# work_table_light.net
KiCad netlist of a schematic drawn in EAGLE
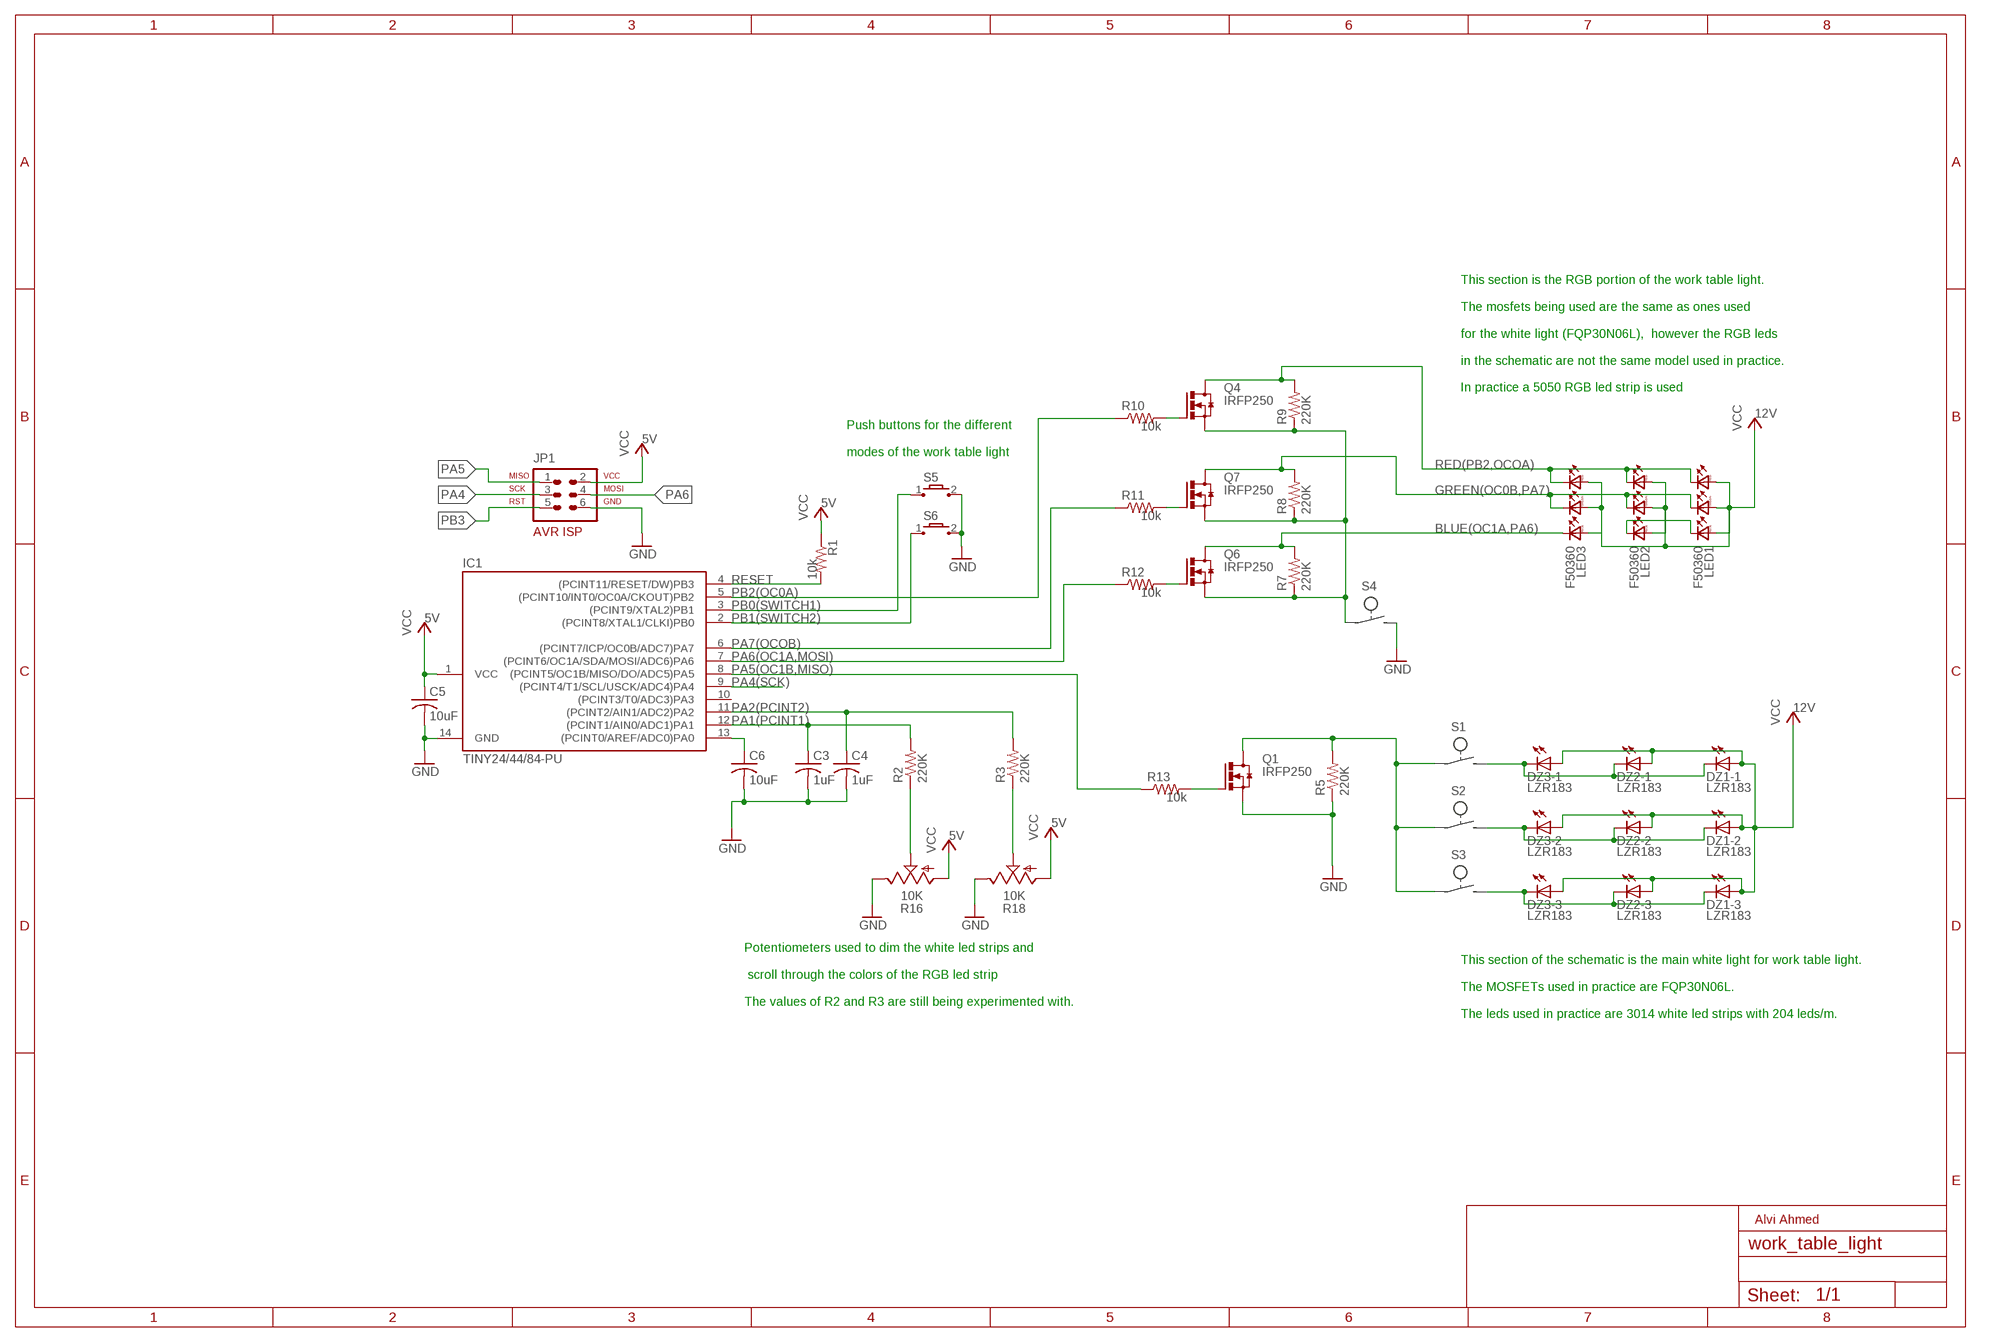
[diagram p0: schematic, sheet 1]

(export (version "E")
  (design (tool "Eeschema 10.0.6"))
  (components
    (comp (ref "C3")
      (value "1uF")
      (footprint "eagle-import:C025-024X044")
      (libsource (lib "eagle-import") (part "C-US025-024X044"))
    )
    (comp (ref "C4")
      (value "1uF")
      (footprint "eagle-import:C025-024X044")
      (libsource (lib "eagle-import") (part "C-US025-024X044"))
    )
    (comp (ref "C5")
      (value "10uF")
      (footprint "eagle-import:C025-024X044")
      (libsource (lib "eagle-import") (part "C-US025-024X044"))
    )
    (comp (ref "C6")
      (value "10uF")
      (footprint "eagle-import:C025-024X044")
      (libsource (lib "eagle-import") (part "C-US025-024X044"))
    )
    (comp (ref "DZ1")
      (value "LZR183")
      (footprint "eagle-import:LZR183")
      (libsource (lib "eagle-import") (part "LZR183"))
    )
    (comp (ref "DZ2")
      (value "LZR183")
      (footprint "eagle-import:LZR183")
      (libsource (lib "eagle-import") (part "LZR183"))
    )
    (comp (ref "DZ3")
      (value "LZR183")
      (footprint "eagle-import:LZR183")
      (libsource (lib "eagle-import") (part "LZR183"))
    )
    (comp (ref "IC1")
      (value "TINY24/44/84-PU")
      (footprint "eagle-import:DIL14")
      (libsource (lib "eagle-import") (part "TINY24/44/84-PU"))
    )
    (comp (ref "JP1")
      (value "AVR-ISP-6VERT")
      (footprint "eagle-import:AVR-ISP-6")
      (libsource (lib "eagle-import") (part "AVR-ISP-6VERT"))
    )
    (comp (ref "LED1")
      (value "F50360")
      (footprint "eagle-import:F50360")
      (libsource (lib "eagle-import") (part "F50360"))
    )
    (comp (ref "LED2")
      (value "F50360")
      (footprint "eagle-import:F50360")
      (libsource (lib "eagle-import") (part "F50360"))
    )
    (comp (ref "LED3")
      (value "F50360")
      (footprint "eagle-import:F50360")
      (libsource (lib "eagle-import") (part "F50360"))
    )
    (comp (ref "Q1")
      (value "IRFP250")
      (footprint "eagle-import:TO-247AD-V")
      (libsource (lib "eagle-import") (part "IRFP250"))
    )
    (comp (ref "Q4")
      (value "IRFP250")
      (footprint "eagle-import:TO-247AD-V")
      (libsource (lib "eagle-import") (part "IRFP250"))
    )
    (comp (ref "Q6")
      (value "IRFP250")
      (footprint "eagle-import:TO-247AD-V")
      (libsource (lib "eagle-import") (part "IRFP250"))
    )
    (comp (ref "Q7")
      (value "IRFP250")
      (footprint "eagle-import:TO-247AD-V")
      (libsource (lib "eagle-import") (part "IRFP250"))
    )
    (comp (ref "R1")
      (value "R-US_0204/5")
      (footprint "eagle-import:0204_5")
      (fields (field (name "SPICEPREFIX") "R") (field (name "SPICEPREFIX_1") "10k"))
      (libsource (lib "eagle-import") (part "R-US_0204/5"))
    )
    (comp (ref "R2")
      (value "220K")
      (footprint "eagle-import:0207_10")
      (libsource (lib "eagle-import") (part "resistor_348_R-US_0207/10"))
    )
    (comp (ref "R3")
      (value "220K")
      (footprint "eagle-import:0207_10")
      (libsource (lib "eagle-import") (part "resistor_348_R-US_0207/10"))
    )
    (comp (ref "R5")
      (value "220K")
      (footprint "eagle-import:0207_10")
      (libsource (lib "eagle-import") (part "resistor_348_R-US_0207/10"))
    )
    (comp (ref "R7")
      (value "220K")
      (footprint "eagle-import:0207_10")
      (libsource (lib "eagle-import") (part "resistor_348_R-US_0207/10"))
    )
    (comp (ref "R8")
      (value "220K")
      (footprint "eagle-import:0207_10")
      (libsource (lib "eagle-import") (part "resistor_348_R-US_0207/10"))
    )
    (comp (ref "R9")
      (value "220K")
      (footprint "eagle-import:0207_10")
      (libsource (lib "eagle-import") (part "resistor_348_R-US_0207/10"))
    )
    (comp (ref "R10")
      (value "R-US_0204/5")
      (footprint "eagle-import:0204_5")
      (fields (field (name "SPICEPREFIX") "R") (field (name "SPICEPREFIX_1") "10k"))
      (libsource (lib "eagle-import") (part "R-US_0204/5"))
    )
    (comp (ref "R11")
      (value "R-US_0204/5")
      (footprint "eagle-import:0204_5")
      (fields (field (name "SPICEPREFIX") "R") (field (name "SPICEPREFIX_1") "10k"))
      (libsource (lib "eagle-import") (part "R-US_0204/5"))
    )
    (comp (ref "R12")
      (value "R-US_0204/5")
      (footprint "eagle-import:0204_5")
      (fields (field (name "SPICEPREFIX") "R") (field (name "SPICEPREFIX_1") "10k"))
      (libsource (lib "eagle-import") (part "R-US_0204/5"))
    )
    (comp (ref "R13")
      (value "R-US_0204/5")
      (footprint "eagle-import:0204_5")
      (fields (field (name "SPICEPREFIX") "R") (field (name "SPICEPREFIX_1") "10k"))
      (libsource (lib "eagle-import") (part "R-US_0204/5"))
    )
    (comp (ref "R16")
      (value "10K")
      (footprint "eagle-import:CIP20C-6MM")
      (libsource (lib "eagle-import") (part "TRIM_US-CIP20C-6MM"))
    )
    (comp (ref "R18")
      (value "10K")
      (footprint "eagle-import:CIP20C-6MM")
      (libsource (lib "eagle-import") (part "TRIM_US-CIP20C-6MM"))
    )
    (comp (ref "S5")
      (value "TL3302-J")
      (footprint "eagle-import:TL3303_J")
      (libsource (lib "eagle-import") (part "TL3302-J"))
    )
    (comp (ref "S6")
      (value "TL3302-J")
      (footprint "eagle-import:TL3303_J")
      (libsource (lib "eagle-import") (part "TL3302-J"))
    )
    (comp (ref "U$1")
      (value "FRAME_AUTH")
      (footprint "eagle-import:FRAME_AUTH")
      (libsource (lib "eagle-import") (part "FRAME_AUTH"))
    )
  )
  (nets
    (net (code "1") (name "/BLUE(OC1A,PA6)") (class "Default")
      (node (ref "LED3") (pin "BC") (pinfunction "BC_BC") (pintype "passive"))
      (node (ref "Q6") (pin "D") (pinfunction "D_D") (pintype "passive"))
      (node (ref "R7") (pin "2") (pinfunction "2_2") (pintype "passive"))
    )
    (net (code "2") (name "/GREEN(OC0B,PA7)") (class "Default")
      (node (ref "LED1") (pin "GC") (pinfunction "GC_GC") (pintype "passive"))
      (node (ref "LED2") (pin "GC") (pinfunction "GC_GC") (pintype "passive"))
      (node (ref "LED3") (pin "GC") (pinfunction "GC_GC") (pintype "passive"))
      (node (ref "Q7") (pin "D") (pinfunction "D_D") (pintype "passive"))
      (node (ref "R8") (pin "2") (pinfunction "2_2") (pintype "passive"))
    )
    (net (code "3") (name "/PA1(PCINT1)") (class "Default")
      (node (ref "C3") (pin "1") (pinfunction "1_1") (pintype "passive"))
      (node (ref "IC1") (pin "12") (pinfunction "(PCINT1/AIN0/ADC1)PA1_12") (pintype "bidirectional"))
      (node (ref "R2") (pin "2") (pinfunction "2_2") (pintype "passive"))
    )
    (net (code "4") (name "/PA2(PCINT2)") (class "Default")
      (node (ref "C4") (pin "1") (pinfunction "1_1") (pintype "passive"))
      (node (ref "IC1") (pin "11") (pinfunction "(PCINT2/AIN1/ADC2)PA2_11") (pintype "bidirectional"))
      (node (ref "R3") (pin "2") (pinfunction "2_2") (pintype "passive"))
    )
    (net (code "5") (name "/PA4(SCK)") (class "Default")
      (node (ref "IC1") (pin "9") (pinfunction "(PCINT4/T1/SCL/USCK/ADC4)PA4_9") (pintype "bidirectional"))
    )
    (net (code "6") (name "/PA5(OC1B,MISO)") (class "Default")
      (node (ref "IC1") (pin "8") (pinfunction "(PCINT5/OC1B/MISO/DO/ADC5)PA5_8") (pintype "bidirectional"))
      (node (ref "R13") (pin "1") (pinfunction "1_1") (pintype "passive"))
    )
    (net (code "7") (name "/PA6(OC1A,MOSI)") (class "Default")
      (node (ref "IC1") (pin "7") (pinfunction "(PCINT6/OC1A/SDA/MOSI/ADC6)PA6_7") (pintype "bidirectional"))
      (node (ref "R12") (pin "1") (pinfunction "1_1") (pintype "passive"))
    )
    (net (code "8") (name "/PA7(OCOB)") (class "Default")
      (node (ref "IC1") (pin "6") (pinfunction "(PCINT7/ICP/OC0B/ADC7)PA7_6") (pintype "bidirectional"))
      (node (ref "R11") (pin "1") (pinfunction "1_1") (pintype "passive"))
    )
    (net (code "9") (name "/PB0(SWITCH1)") (class "Default")
      (node (ref "IC1") (pin "3") (pinfunction "(PCINT9/XTAL2)PB1_3") (pintype "bidirectional"))
      (node (ref "S5") (pin "1") (pinfunction "1_1") (pintype "passive"))
    )
    (net (code "10") (name "/PB1(SWITCH2)") (class "Default")
      (node (ref "IC1") (pin "2") (pinfunction "(PCINT8/XTAL1/CLKI)PB0_2") (pintype "bidirectional"))
      (node (ref "S6") (pin "1") (pinfunction "1_1") (pintype "passive"))
    )
    (net (code "11") (name "/PB2(OC0A)") (class "Default")
      (node (ref "IC1") (pin "5") (pinfunction "(PCINT10/INT0/OC0A/CKOUT)PB2_5") (pintype "bidirectional"))
      (node (ref "R10") (pin "1") (pinfunction "1_1") (pintype "passive"))
    )
    (net (code "12") (name "/RED(PB2,OCOA)") (class "Default")
      (node (ref "LED1") (pin "RC") (pinfunction "RC_RC") (pintype "passive"))
      (node (ref "LED2") (pin "RC") (pinfunction "RC_RC") (pintype "passive"))
      (node (ref "LED3") (pin "RC") (pinfunction "RC_RC") (pintype "passive"))
      (node (ref "Q4") (pin "D") (pinfunction "D_D") (pintype "passive"))
      (node (ref "R9") (pin "2") (pinfunction "2_2") (pintype "passive"))
    )
    (net (code "13") (name "/RESET") (class "Default")
      (node (ref "IC1") (pin "4") (pinfunction "(PCINT11/RESET/DW)PB3_4") (pintype "bidirectional"))
      (node (ref "R1") (pin "2") (pinfunction "2_2") (pintype "passive"))
    )
    (net (code "14") (name "GND") (class "Default")
      (node (ref "C3") (pin "2") (pinfunction "2_2") (pintype "passive"))
      (node (ref "C4") (pin "2") (pinfunction "2_2") (pintype "passive"))
      (node (ref "C5") (pin "2") (pinfunction "2_2") (pintype "passive"))
      (node (ref "C6") (pin "2") (pinfunction "2_2") (pintype "passive"))
      (node (ref "IC1") (pin "14") (pinfunction "GND_14") (pintype "power_in"))
      (node (ref "JP1") (pin "6") (pinfunction "6_6") (pintype "passive"))
      (node (ref "Q1") (pin "S") (pinfunction "S_S") (pintype "passive"))
      (node (ref "R16") (pin "E") (pinfunction "E_E") (pintype "passive"))
      (node (ref "R18") (pin "E") (pinfunction "E_E") (pintype "passive"))
      (node (ref "R5") (pin "1") (pinfunction "1_1") (pintype "passive"))
      (node (ref "S5") (pin "2") (pinfunction "2_2") (pintype "passive"))
      (node (ref "S6") (pin "2") (pinfunction "2_2") (pintype "passive"))
    )
    (net (code "15") (name "Net-(DZ1A-C)") (class "Default")
      (node (ref "DZ1") (pin "K1") (pinfunction "C_K1") (pintype "passive"))
      (node (ref "DZ2") (pin "K1") (pinfunction "C_K1") (pintype "passive"))
      (node (ref "DZ3") (pin "K1") (pinfunction "C_K1") (pintype "passive"))
    )
    (net (code "16") (name "Net-(DZ1B-C)") (class "Default")
      (node (ref "DZ1") (pin "K2") (pinfunction "C_K2") (pintype "passive"))
      (node (ref "DZ2") (pin "K2") (pinfunction "C_K2") (pintype "passive"))
      (node (ref "DZ3") (pin "K2") (pinfunction "C_K2") (pintype "passive"))
    )
    (net (code "17") (name "Net-(DZ1C-C)") (class "Default")
      (node (ref "DZ1") (pin "K3") (pinfunction "C_K3") (pintype "passive"))
      (node (ref "DZ2") (pin "K3") (pinfunction "C_K3") (pintype "passive"))
      (node (ref "DZ3") (pin "K3") (pinfunction "C_K3") (pintype "passive"))
    )
    (net (code "18") (name "Net-(IC1-(PCINT0{slash}AREF{slash}ADC0)PA0)") (class "Default")
      (node (ref "C6") (pin "1") (pinfunction "1_1") (pintype "passive"))
      (node (ref "IC1") (pin "13") (pinfunction "(PCINT0/AREF/ADC0)PA0_13") (pintype "bidirectional"))
    )
    (net (code "19") (name "Net-(LED1-PadBC)") (class "Default")
      (node (ref "LED1") (pin "BC") (pinfunction "BC_BC") (pintype "passive"))
      (node (ref "LED2") (pin "BC") (pinfunction "BC_BC") (pintype "passive"))
    )
    (net (code "20") (name "Net-(Q1-PadD)") (class "Default")
      (node (ref "Q1") (pin "D") (pinfunction "D_D") (pintype "passive"))
      (node (ref "R5") (pin "2") (pinfunction "2_2") (pintype "passive"))
    )
    (net (code "21") (name "Net-(Q1-PadG)") (class "Default")
      (node (ref "Q1") (pin "G") (pinfunction "G_G") (pintype "passive"))
      (node (ref "R13") (pin "2") (pinfunction "2_2") (pintype "passive"))
    )
    (net (code "22") (name "Net-(Q4-PadG)") (class "Default")
      (node (ref "Q4") (pin "G") (pinfunction "G_G") (pintype "passive"))
      (node (ref "R10") (pin "2") (pinfunction "2_2") (pintype "passive"))
    )
    (net (code "23") (name "Net-(Q4-PadS)") (class "Default")
      (node (ref "Q4") (pin "S") (pinfunction "S_S") (pintype "passive"))
      (node (ref "Q6") (pin "S") (pinfunction "S_S") (pintype "passive"))
      (node (ref "Q7") (pin "S") (pinfunction "S_S") (pintype "passive"))
      (node (ref "R7") (pin "1") (pinfunction "1_1") (pintype "passive"))
      (node (ref "R8") (pin "1") (pinfunction "1_1") (pintype "passive"))
      (node (ref "R9") (pin "1") (pinfunction "1_1") (pintype "passive"))
    )
    (net (code "24") (name "Net-(Q6-PadG)") (class "Default")
      (node (ref "Q6") (pin "G") (pinfunction "G_G") (pintype "passive"))
      (node (ref "R12") (pin "2") (pinfunction "2_2") (pintype "passive"))
    )
    (net (code "25") (name "Net-(Q7-PadG)") (class "Default")
      (node (ref "Q7") (pin "G") (pinfunction "G_G") (pintype "passive"))
      (node (ref "R11") (pin "2") (pinfunction "2_2") (pintype "passive"))
    )
    (net (code "26") (name "Net-(R16-PadS)") (class "Default")
      (node (ref "R16") (pin "S") (pinfunction "S_S") (pintype "passive"))
      (node (ref "R2") (pin "1") (pinfunction "1_1") (pintype "passive"))
    )
    (net (code "27") (name "Net-(R18-PadS)") (class "Default")
      (node (ref "R18") (pin "S") (pinfunction "S_S") (pintype "passive"))
      (node (ref "R3") (pin "1") (pinfunction "1_1") (pintype "passive"))
    )
    (net (code "28") (name "PA4") (class "Default")
      (node (ref "JP1") (pin "3") (pinfunction "3_3") (pintype "passive"))
    )
    (net (code "29") (name "PA5") (class "Default")
      (node (ref "JP1") (pin "1") (pinfunction "1_1") (pintype "passive"))
    )
    (net (code "30") (name "PA6") (class "Default")
      (node (ref "JP1") (pin "4") (pinfunction "4_4") (pintype "passive"))
    )
    (net (code "31") (name "PB3") (class "Default")
      (node (ref "JP1") (pin "5") (pinfunction "5_5") (pintype "passive"))
    )
    (net (code "32") (name "VCC") (class "Default")
      (node (ref "C5") (pin "1") (pinfunction "1_1") (pintype "passive"))
      (node (ref "DZ1") (pin "A1") (pinfunction "A_A1") (pintype "passive"))
      (node (ref "DZ1") (pin "A2") (pinfunction "A_A2") (pintype "passive"))
      (node (ref "DZ1") (pin "A3") (pinfunction "A_A3") (pintype "passive"))
      (node (ref "DZ2") (pin "A1") (pinfunction "A_A1") (pintype "passive"))
      (node (ref "DZ2") (pin "A2") (pinfunction "A_A2") (pintype "passive"))
      (node (ref "DZ2") (pin "A3") (pinfunction "A_A3") (pintype "passive"))
      (node (ref "DZ3") (pin "A1") (pinfunction "A_A1") (pintype "passive"))
      (node (ref "DZ3") (pin "A2") (pinfunction "A_A2") (pintype "passive"))
      (node (ref "DZ3") (pin "A3") (pinfunction "A_A3") (pintype "passive"))
      (node (ref "IC1") (pin "1") (pinfunction "VCC_1") (pintype "power_in"))
      (node (ref "JP1") (pin "2") (pinfunction "2_2") (pintype "passive"))
      (node (ref "LED1") (pin "BA") (pinfunction "BA_BA") (pintype "passive"))
      (node (ref "LED1") (pin "GA") (pinfunction "GA_GA") (pintype "passive"))
      (node (ref "LED1") (pin "RA") (pinfunction "RA_RA") (pintype "passive"))
      (node (ref "LED2") (pin "BA") (pinfunction "BA_BA") (pintype "passive"))
      (node (ref "LED2") (pin "GA") (pinfunction "GA_GA") (pintype "passive"))
      (node (ref "LED2") (pin "RA") (pinfunction "RA_RA") (pintype "passive"))
      (node (ref "LED3") (pin "BA") (pinfunction "BA_BA") (pintype "passive"))
      (node (ref "LED3") (pin "GA") (pinfunction "GA_GA") (pintype "passive"))
      (node (ref "LED3") (pin "RA") (pinfunction "RA_RA") (pintype "passive"))
      (node (ref "R1") (pin "1") (pinfunction "1_1") (pintype "passive"))
      (node (ref "R16") (pin "A") (pinfunction "A_A") (pintype "passive"))
      (node (ref "R18") (pin "A") (pinfunction "A_A") (pintype "passive"))
    )
    (net (code "33") (name "unconnected-(IC1-(PCINT3{slash}T0{slash}ADC3)PA3-Pad10)") (class "Default")
      (node (ref "IC1") (pin "10") (pinfunction "(PCINT3/T0/ADC3)PA3_10") (pintype "bidirectional"))
    )
  )
)
